# Main.net
KiCad netlist of a schematic drawn in Altium Designer
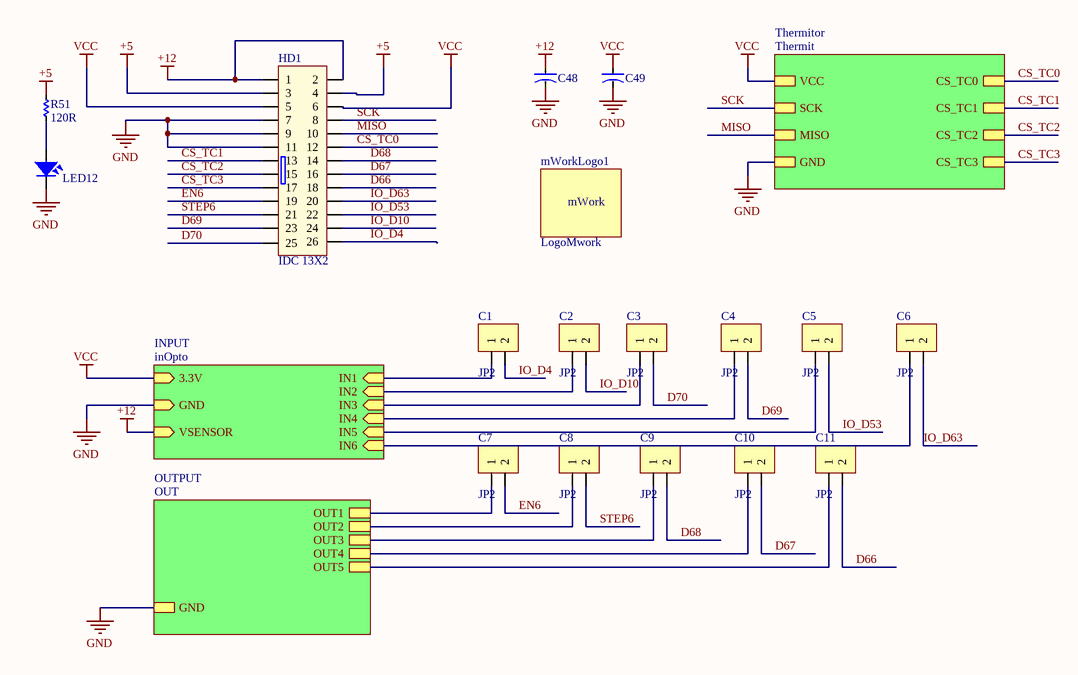
[diagram p0: Main.SchDoc]

(export (version "E")
  (design (tool "Eeschema 10.0.6"))
  (components
    (comp (ref "C1")
      (value "JP2")
      (footprint "JP2-CLOSED")
      (description "WR-PHD 2.54 mm Angled Socket Header")
      (fields
        (field (name "MANUFACTURER") "Würth Elektronik eiSos GmbH")
        (field (name "PARTNO") "613002143121")
        (field (name "CREATED BY") "Karrer Zheng")
      )
      (libsource (lib "LIBRARY") (part "JP2"))
    )
    (comp (ref "C2")
      (value "JP2")
      (footprint "JP2-CLOSED")
      (description "WR-PHD 2.54 mm Angled Socket Header")
      (fields
        (field (name "MANUFACTURER") "Würth Elektronik eiSos GmbH")
        (field (name "PARTNO") "613002143121")
        (field (name "CREATED BY") "Karrer Zheng")
      )
      (libsource (lib "LIBRARY") (part "JP2"))
    )
    (comp (ref "C3")
      (value "JP2")
      (footprint "JP2-CLOSED")
      (description "WR-PHD 2.54 mm Angled Socket Header")
      (fields
        (field (name "MANUFACTURER") "Würth Elektronik eiSos GmbH")
        (field (name "PARTNO") "613002143121")
        (field (name "CREATED BY") "Karrer Zheng")
      )
      (libsource (lib "LIBRARY") (part "JP2"))
    )
    (comp (ref "C4")
      (value "JP2")
      (footprint "JP2-CLOSED")
      (description "WR-PHD 2.54 mm Angled Socket Header")
      (fields
        (field (name "MANUFACTURER") "Würth Elektronik eiSos GmbH")
        (field (name "PARTNO") "613002143121")
        (field (name "CREATED BY") "Karrer Zheng")
      )
      (libsource (lib "LIBRARY") (part "JP2"))
    )
    (comp (ref "C5")
      (value "JP2")
      (footprint "JP2-CLOSED")
      (description "WR-PHD 2.54 mm Angled Socket Header")
      (fields
        (field (name "MANUFACTURER") "Würth Elektronik eiSos GmbH")
        (field (name "PARTNO") "613002143121")
        (field (name "CREATED BY") "Karrer Zheng")
      )
      (libsource (lib "LIBRARY") (part "JP2"))
    )
    (comp (ref "C6")
      (value "JP2")
      (footprint "JP2-CLOSED")
      (description "WR-PHD 2.54 mm Angled Socket Header")
      (fields
        (field (name "MANUFACTURER") "Würth Elektronik eiSos GmbH")
        (field (name "PARTNO") "613002143121")
        (field (name "CREATED BY") "Karrer Zheng")
      )
      (libsource (lib "LIBRARY") (part "JP2"))
    )
    (comp (ref "C7")
      (value "JP2")
      (footprint "JP2-CLOSED")
      (description "WR-PHD 2.54 mm Angled Socket Header")
      (fields
        (field (name "MANUFACTURER") "Würth Elektronik eiSos GmbH")
        (field (name "PARTNO") "613002143121")
        (field (name "CREATED BY") "Karrer Zheng")
      )
      (libsource (lib "LIBRARY") (part "JP2"))
    )
    (comp (ref "C8")
      (value "JP2")
      (footprint "JP2-CLOSED")
      (description "WR-PHD 2.54 mm Angled Socket Header")
      (fields
        (field (name "MANUFACTURER") "Würth Elektronik eiSos GmbH")
        (field (name "PARTNO") "613002143121")
        (field (name "CREATED BY") "Karrer Zheng")
      )
      (libsource (lib "LIBRARY") (part "JP2"))
    )
    (comp (ref "C9")
      (value "JP2")
      (footprint "JP2-CLOSED")
      (description "WR-PHD 2.54 mm Angled Socket Header")
      (fields
        (field (name "MANUFACTURER") "Würth Elektronik eiSos GmbH")
        (field (name "PARTNO") "613002143121")
        (field (name "CREATED BY") "Karrer Zheng")
      )
      (libsource (lib "LIBRARY") (part "JP2"))
    )
    (comp (ref "C10")
      (value "JP2")
      (footprint "JP2-CLOSED")
      (description "WR-PHD 2.54 mm Angled Socket Header")
      (fields
        (field (name "MANUFACTURER") "Würth Elektronik eiSos GmbH")
        (field (name "PARTNO") "613002143121")
        (field (name "CREATED BY") "Karrer Zheng")
      )
      (libsource (lib "LIBRARY") (part "JP2"))
    )
    (comp (ref "C11")
      (value "JP2")
      (footprint "JP2-CLOSED")
      (description "WR-PHD 2.54 mm Angled Socket Header")
      (fields
        (field (name "MANUFACTURER") "Würth Elektronik eiSos GmbH")
        (field (name "PARTNO") "613002143121")
        (field (name "CREATED BY") "Karrer Zheng")
      )
      (libsource (lib "LIBRARY") (part "JP2"))
    )
    (comp (ref "C48")
      (value "CN-ALU-SMD")
      (footprint "CAP-ALU-SMD-F")
      (description "Polarized Capacitor (Axial)")
      (fields (field (name "PUBLISHER") "Altium Limited"))
      (libsource (lib "LIBRARY") (part "CN-ALU-SMD"))
    )
    (comp (ref "C49")
      (value "CN-ALU-SMD")
      (footprint "CAP-ALU-SMD-F")
      (description "Polarized Capacitor (Axial)")
      (fields (field (name "PUBLISHER") "Altium Limited"))
      (libsource (lib "LIBRARY") (part "CN-ALU-SMD"))
    )
    (comp (ref "HD1")
      (value "IDC 13X2")
      (footprint "IDC26-B")
      (description "IDC 13x2")
      (libsource (lib "BanLinhKien") (part "IDC 13X2"))
    )
    (comp (ref "LED12") (value "LED") (footprint "LED-0805-Red") (libsource (lib "LIBRARY") (part "LED SMD")))
    (comp (ref "mWorkLogo1")
      (value "LogoMwork")
      (footprint "LogoMwork30*12")
      (libsource (lib "nhan") (part "LogoMwork"))
    )
    (comp (ref "R51") (value "120R") (footprint "RES-SMD-0603_BIG") (libsource (lib "nhan") (part "R")))
  )
  (nets
    (net (code "1") (name "+5") (class "Default")
      (node (ref "HD1") (pin "3") (pinfunction "3_3") (pintype "passive"))
      (node (ref "HD1") (pin "4") (pinfunction "4_4") (pintype "passive"))
      (node (ref "R51") (pin "2") (pinfunction "2_2") (pintype "passive"))
    )
    (net (code "2") (name "+12") (class "Default")
      (node (ref "C48") (pin "1") (pinfunction "1_1") (pintype "passive"))
      (node (ref "HD1") (pin "1") (pinfunction "1_1") (pintype "passive"))
      (node (ref "HD1") (pin "2") (pinfunction "2_2") (pintype "passive"))
    )
    (net (code "3") (name "/CS_TC0") (class "Default")
      (node (ref "HD1") (pin "12") (pinfunction "12_12") (pintype "passive"))
    )
    (net (code "4") (name "/CS_TC1") (class "Default")
      (node (ref "HD1") (pin "13") (pinfunction "13_13") (pintype "passive"))
    )
    (net (code "5") (name "/CS_TC2") (class "Default")
      (node (ref "HD1") (pin "15") (pinfunction "15_15") (pintype "passive"))
    )
    (net (code "6") (name "/CS_TC3") (class "Default")
      (node (ref "HD1") (pin "17") (pinfunction "17_17") (pintype "passive"))
    )
    (net (code "7") (name "/D66") (class "Default")
      (node (ref "C11") (pin "2") (pinfunction "2_2") (pintype "passive"))
      (node (ref "HD1") (pin "18") (pinfunction "18_18") (pintype "passive"))
    )
    (net (code "8") (name "/D67") (class "Default")
      (node (ref "C10") (pin "2") (pinfunction "2_2") (pintype "passive"))
      (node (ref "HD1") (pin "16") (pinfunction "16_16") (pintype "passive"))
    )
    (net (code "9") (name "/D68") (class "Default")
      (node (ref "C9") (pin "2") (pinfunction "2_2") (pintype "passive"))
      (node (ref "HD1") (pin "14") (pinfunction "14_14") (pintype "passive"))
    )
    (net (code "10") (name "/D69") (class "Default")
      (node (ref "C4") (pin "2") (pinfunction "2_2") (pintype "passive"))
      (node (ref "HD1") (pin "23") (pinfunction "23_23") (pintype "passive"))
    )
    (net (code "11") (name "/D70") (class "Default")
      (node (ref "C3") (pin "2") (pinfunction "2_2") (pintype "passive"))
      (node (ref "HD1") (pin "25") (pinfunction "25_25") (pintype "passive"))
    )
    (net (code "12") (name "/EN6") (class "Default")
      (node (ref "C7") (pin "2") (pinfunction "2_2") (pintype "passive"))
      (node (ref "HD1") (pin "19") (pinfunction "19_19") (pintype "passive"))
    )
    (net (code "13") (name "/IN1") (class "Default")
      (node (ref "C1") (pin "1") (pinfunction "1_1") (pintype "passive"))
    )
    (net (code "14") (name "/IN2") (class "Default")
      (node (ref "C2") (pin "1") (pinfunction "1_1") (pintype "passive"))
    )
    (net (code "15") (name "/IN3") (class "Default")
      (node (ref "C3") (pin "1") (pinfunction "1_1") (pintype "passive"))
    )
    (net (code "16") (name "/IN4") (class "Default")
      (node (ref "C4") (pin "1") (pinfunction "1_1") (pintype "passive"))
    )
    (net (code "17") (name "/IN5") (class "Default")
      (node (ref "C5") (pin "1") (pinfunction "1_1") (pintype "passive"))
    )
    (net (code "18") (name "/IN6") (class "Default")
      (node (ref "C6") (pin "1") (pinfunction "1_1") (pintype "passive"))
    )
    (net (code "19") (name "/IO_D4") (class "Default")
      (node (ref "C1") (pin "2") (pinfunction "2_2") (pintype "passive"))
      (node (ref "HD1") (pin "26") (pinfunction "26_26") (pintype "passive"))
    )
    (net (code "20") (name "/IO_D10") (class "Default")
      (node (ref "C2") (pin "2") (pinfunction "2_2") (pintype "passive"))
      (node (ref "HD1") (pin "24") (pinfunction "24_24") (pintype "passive"))
    )
    (net (code "21") (name "/IO_D53") (class "Default")
      (node (ref "C5") (pin "2") (pinfunction "2_2") (pintype "passive"))
      (node (ref "HD1") (pin "22") (pinfunction "22_22") (pintype "passive"))
    )
    (net (code "22") (name "/IO_D63") (class "Default")
      (node (ref "C6") (pin "2") (pinfunction "2_2") (pintype "passive"))
      (node (ref "HD1") (pin "20") (pinfunction "20_20") (pintype "passive"))
    )
    (net (code "23") (name "/MISO") (class "Default")
      (node (ref "HD1") (pin "10") (pinfunction "10_10") (pintype "passive"))
    )
    (net (code "24") (name "/OUT1") (class "Default")
      (node (ref "C7") (pin "1") (pinfunction "1_1") (pintype "passive"))
    )
    (net (code "25") (name "/OUT2") (class "Default")
      (node (ref "C8") (pin "1") (pinfunction "1_1") (pintype "passive"))
    )
    (net (code "26") (name "/OUT3") (class "Default")
      (node (ref "C9") (pin "1") (pinfunction "1_1") (pintype "passive"))
    )
    (net (code "27") (name "/OUT4") (class "Default")
      (node (ref "C10") (pin "1") (pinfunction "1_1") (pintype "passive"))
    )
    (net (code "28") (name "/OUT5") (class "Default")
      (node (ref "C11") (pin "1") (pinfunction "1_1") (pintype "passive"))
    )
    (net (code "29") (name "/SCK") (class "Default")
      (node (ref "HD1") (pin "8") (pinfunction "8_8") (pintype "passive"))
    )
    (net (code "30") (name "/STEP6") (class "Default")
      (node (ref "C8") (pin "2") (pinfunction "2_2") (pintype "passive"))
      (node (ref "HD1") (pin "21") (pinfunction "21_21") (pintype "passive"))
    )
    (net (code "31") (name "GND") (class "Default")
      (node (ref "C48") (pin "2") (pinfunction "2_2") (pintype "passive"))
      (node (ref "C49") (pin "2") (pinfunction "2_2") (pintype "passive"))
      (node (ref "HD1") (pin "11") (pinfunction "11_11") (pintype "passive"))
      (node (ref "HD1") (pin "7") (pinfunction "7_7") (pintype "passive"))
      (node (ref "HD1") (pin "9") (pinfunction "9_9") (pintype "passive"))
      (node (ref "LED12") (pin "2") (pinfunction "2_2") (pintype "passive"))
    )
    (net (code "32") (name "Net-(LED12-Pad1)") (class "Default")
      (node (ref "LED12") (pin "1") (pinfunction "1_1") (pintype "passive"))
      (node (ref "R51") (pin "1") (pinfunction "1_1") (pintype "passive"))
    )
    (net (code "33") (name "VCC") (class "Default")
      (node (ref "C49") (pin "1") (pinfunction "1_1") (pintype "passive"))
      (node (ref "HD1") (pin "5") (pinfunction "5_5") (pintype "passive"))
      (node (ref "HD1") (pin "6") (pinfunction "6_6") (pintype "passive"))
    )
  )
)
